# Design1.net
KiCad netlist of a schematic drawn in EAGLE
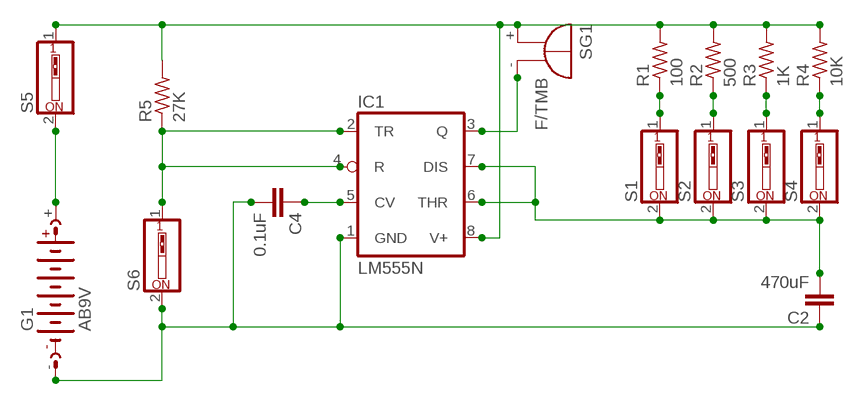
[diagram p0: schematic, sheet 1]

(export (version "E")
  (design (tool "Eeschema 10.0.6"))
  (components
    (comp (ref "C2")
      (value "470uF")
      (footprint "eagle-import:C5B2.5")
      (libsource (lib "eagle-import") (part "C5/2.5"))
    )
    (comp (ref "C4")
      (value "0.1uF")
      (footprint "eagle-import:C5B2.5")
      (libsource (lib "eagle-import") (part "C5/2.5"))
    )
    (comp (ref "G1")
      (value "AB9V")
      (footprint "eagle-import:AB9V")
      (libsource (lib "eagle-import") (part "AB9V"))
    )
    (comp (ref "IC1")
      (value "LM555N")
      (footprint "eagle-import:DIL08")
      (libsource (lib "eagle-import") (part "555NLM"))
    )
    (comp (ref "R1")
      (value "100")
      (footprint "eagle-import:0207_12")
      (libsource (lib "eagle-import") (part "R-US_0207/12"))
    )
    (comp (ref "R2")
      (value "500")
      (footprint "eagle-import:0207_12")
      (libsource (lib "eagle-import") (part "R-US_0207/12"))
    )
    (comp (ref "R3")
      (value "1K")
      (footprint "eagle-import:0207_12")
      (libsource (lib "eagle-import") (part "R-US_0207/12"))
    )
    (comp (ref "R4")
      (value "10K")
      (footprint "eagle-import:0207_12")
      (libsource (lib "eagle-import") (part "R-US_0207/12"))
    )
    (comp (ref "R5")
      (value "27K")
      (footprint "eagle-import:0207_12")
      (libsource (lib "eagle-import") (part "resistor_348_R-US_0207/12"))
    )
    (comp (ref "S1")
      (value "SW_DIP-1")
      (footprint "eagle-import:EDG-01")
      (libsource (lib "eagle-import") (part "SW_DIP-1"))
    )
    (comp (ref "S2")
      (value "SW_DIP-1")
      (footprint "eagle-import:EDG-01")
      (libsource (lib "eagle-import") (part "SW_DIP-1"))
    )
    (comp (ref "S3")
      (value "SW_DIP-1")
      (footprint "eagle-import:EDG-01")
      (libsource (lib "eagle-import") (part "SW_DIP-1"))
    )
    (comp (ref "S4")
      (value "SW_DIP-1")
      (footprint "eagle-import:EDG-01")
      (libsource (lib "eagle-import") (part "SW_DIP-1"))
    )
    (comp (ref "S5")
      (value "SW_DIP-1")
      (footprint "eagle-import:EDG-01")
      (libsource (lib "eagle-import") (part "SW_DIP-1"))
    )
    (comp (ref "S6")
      (value "SW_DIP-1")
      (footprint "eagle-import:EDG-01")
      (libsource (lib "eagle-import") (part "SW_DIP-1"))
    )
    (comp (ref "SG1")
      (value "F/TMB")
      (footprint "eagle-import:F_TMB")
      (libsource (lib "eagle-import") (part "F/TMB"))
    )
  )
  (nets
    (net (code "1") (name "Net-(G1-Pad+)") (class "Default")
      (node (ref "G1") (pin "+") (pinfunction "+_+") (pintype "passive"))
      (node (ref "S5") (pin "2") (pinfunction "2_2") (pintype "passive"))
    )
    (net (code "2") (name "Net-(IC1-CV)") (class "Default")
      (node (ref "C4") (pin "1") (pinfunction "1_1") (pintype "passive"))
      (node (ref "IC1") (pin "5") (pinfunction "CV_5") (pintype "input"))
    )
    (net (code "3") (name "Net-(IC1-DIS)") (class "Default")
      (node (ref "C2") (pin "2") (pinfunction "2_2") (pintype "passive"))
      (node (ref "IC1") (pin "6") (pinfunction "THR_6") (pintype "input"))
      (node (ref "IC1") (pin "7") (pinfunction "DIS_7") (pintype "input"))
      (node (ref "S1") (pin "2") (pinfunction "2_2") (pintype "passive"))
      (node (ref "S2") (pin "2") (pinfunction "2_2") (pintype "passive"))
      (node (ref "S3") (pin "2") (pinfunction "2_2") (pintype "passive"))
      (node (ref "S4") (pin "2") (pinfunction "2_2") (pintype "passive"))
    )
    (net (code "4") (name "Net-(IC1-GND)") (class "Default")
      (node (ref "C2") (pin "1") (pinfunction "1_1") (pintype "passive"))
      (node (ref "C4") (pin "2") (pinfunction "2_2") (pintype "passive"))
      (node (ref "G1") (pin "-") (pinfunction "-_-") (pintype "passive"))
      (node (ref "IC1") (pin "1") (pinfunction "GND_1") (pintype "power_in"))
      (node (ref "S6") (pin "2") (pinfunction "2_2") (pintype "passive"))
    )
    (net (code "5") (name "Net-(IC1-Q)") (class "Default")
      (node (ref "IC1") (pin "3") (pinfunction "Q_3") (pintype "output"))
      (node (ref "SG1") (pin "-") (pinfunction "-_-") (pintype "passive"))
    )
    (net (code "6") (name "Net-(IC1-R)") (class "Default")
      (node (ref "IC1") (pin "2") (pinfunction "TR_2") (pintype "input"))
      (node (ref "IC1") (pin "4") (pinfunction "R_4") (pintype "input"))
      (node (ref "R5") (pin "1") (pinfunction "1_1") (pintype "passive"))
      (node (ref "S6") (pin "1") (pinfunction "1_1") (pintype "passive"))
    )
    (net (code "7") (name "Net-(IC1-V+)") (class "Default")
      (node (ref "IC1") (pin "8") (pinfunction "V+_8") (pintype "power_in"))
      (node (ref "R1") (pin "2") (pinfunction "2_2") (pintype "passive"))
      (node (ref "R2") (pin "2") (pinfunction "2_2") (pintype "passive"))
      (node (ref "R3") (pin "2") (pinfunction "2_2") (pintype "passive"))
      (node (ref "R4") (pin "2") (pinfunction "2_2") (pintype "passive"))
      (node (ref "R5") (pin "2") (pinfunction "2_2") (pintype "passive"))
      (node (ref "S5") (pin "1") (pinfunction "1_1") (pintype "passive"))
      (node (ref "SG1") (pin "+") (pinfunction "+_+") (pintype "passive"))
    )
    (net (code "8") (name "Net-(R1-Pad1)") (class "Default")
      (node (ref "R1") (pin "1") (pinfunction "1_1") (pintype "passive"))
      (node (ref "S1") (pin "1") (pinfunction "1_1") (pintype "passive"))
    )
    (net (code "9") (name "Net-(R2-Pad1)") (class "Default")
      (node (ref "R2") (pin "1") (pinfunction "1_1") (pintype "passive"))
      (node (ref "S2") (pin "1") (pinfunction "1_1") (pintype "passive"))
    )
    (net (code "10") (name "Net-(R3-Pad1)") (class "Default")
      (node (ref "R3") (pin "1") (pinfunction "1_1") (pintype "passive"))
      (node (ref "S3") (pin "1") (pinfunction "1_1") (pintype "passive"))
    )
    (net (code "11") (name "Net-(R4-Pad1)") (class "Default")
      (node (ref "R4") (pin "1") (pinfunction "1_1") (pintype "passive"))
      (node (ref "S4") (pin "1") (pinfunction "1_1") (pintype "passive"))
    )
  )
)
